# rock.net
KiCad netlist of a schematic drawn in Altium Designer
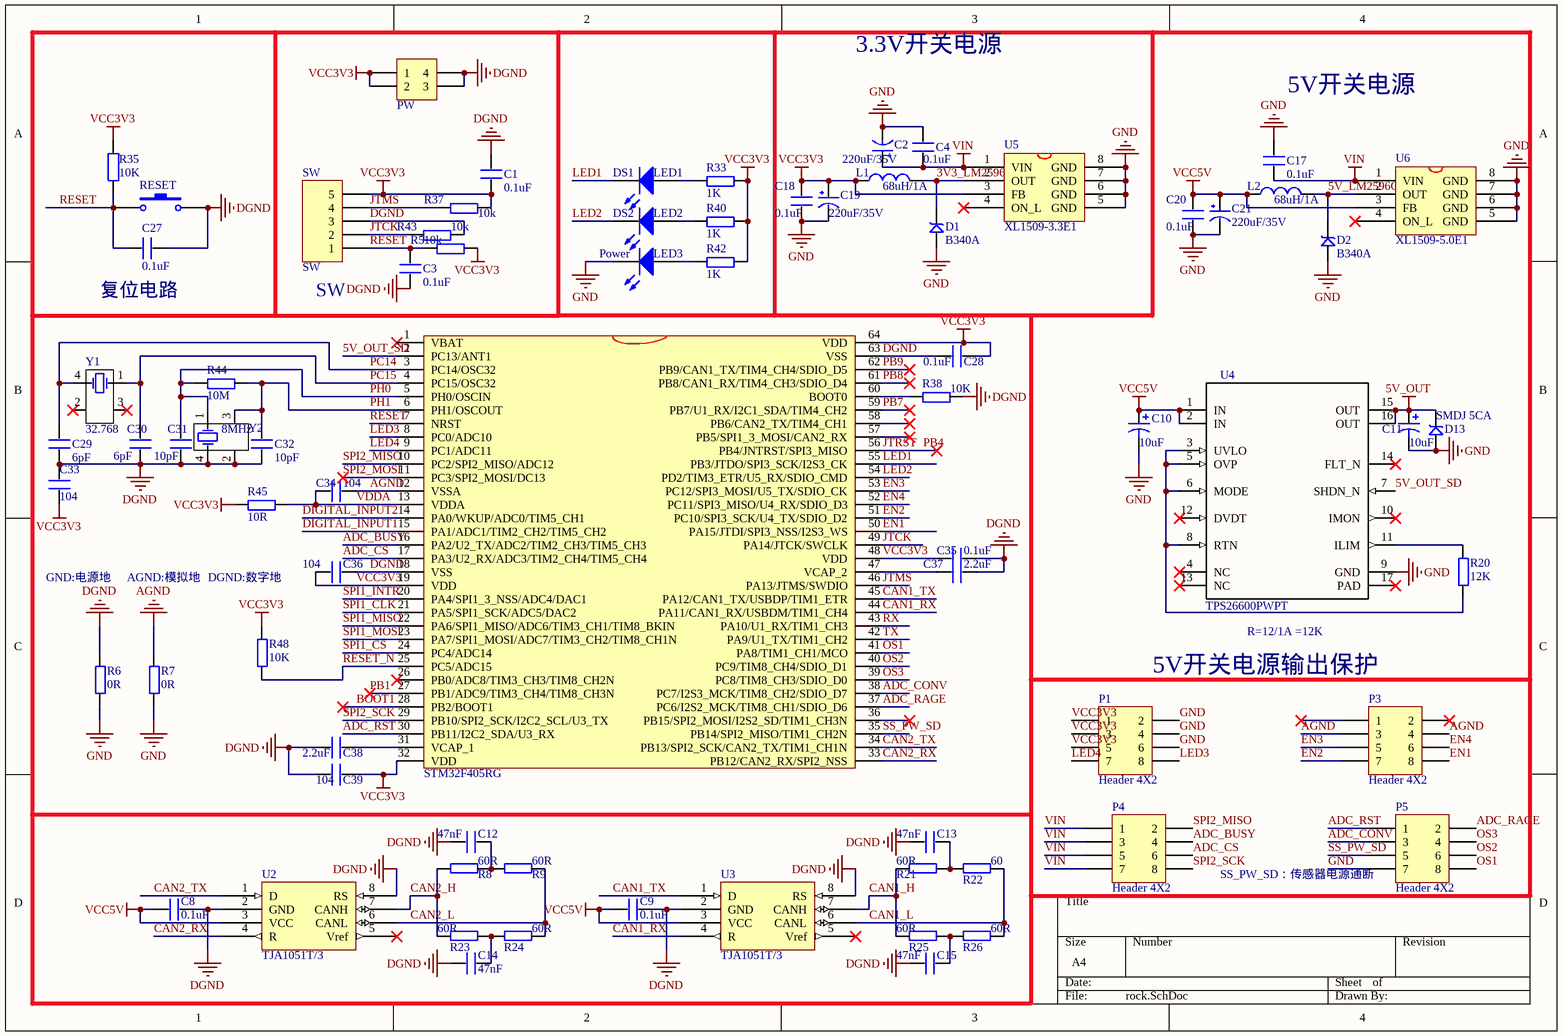
[diagram p0: rock.SchDoc]

(export (version "E")
  (design (tool "Eeschema 10.0.6"))
  (components
    (comp (ref "C1") (value "0.1uF") (footprint "0603") (libsource (lib "MiniSTM32 V3.0封装库") (part "C")))
    (comp (ref "C2")
      (value "220uF/35V")
      (footprint "C-RB-S8")
      (libsource (lib "MiniSTM32 V3.0封装库") (part "CAP"))
    )
    (comp (ref "C3") (value "0.1uF") (footprint "0603") (libsource (lib "MiniSTM32 V3.0封装库") (part "C")))
    (comp (ref "C4") (value "0.1uF") (footprint "0603") (libsource (lib "MiniSTM32 V3.0封装库") (part "C")))
    (comp (ref "C8") (value "0.1uF") (footprint "0603") (libsource (lib "MiniSTM32 V3.0封装库") (part "C")))
    (comp (ref "C9") (value "0.1uF") (footprint "0603") (libsource (lib "MiniSTM32 V3.0封装库") (part "C")))
    (comp (ref "C10")
      (value "10uF")
      (footprint "CAP-3216")
      (description "Polarized Capacitor (Surface Mount)")
      (fields (field (name "Comment") "Cap Pol3") (field (name "PUBLISHER") "Altium Limited"))
      (libsource (lib "Miscellaneous Devices") (part "Cap Pol3"))
    )
    (comp (ref "C11")
      (value "10uF")
      (footprint "CAP-3216")
      (description "Polarized Capacitor (Surface Mount)")
      (fields (field (name "Comment") "Cap Pol3") (field (name "PUBLISHER") "Altium Limited"))
      (libsource (lib "Miscellaneous Devices") (part "Cap Pol3"))
    )
    (comp (ref "C12") (value "47nF") (footprint "0603") (libsource (lib "MiniSTM32 V3.0封装库") (part "C")))
    (comp (ref "C13") (value "47nF") (footprint "0603") (libsource (lib "MiniSTM32 V3.0封装库") (part "C")))
    (comp (ref "C14") (value "47nF") (footprint "0603") (libsource (lib "MiniSTM32 V3.0封装库") (part "C")))
    (comp (ref "C15") (value "47nF") (footprint "0603") (libsource (lib "MiniSTM32 V3.0封装库") (part "C")))
    (comp (ref "C17") (value "0.1uF") (footprint "0603") (libsource (lib "MiniSTM32 V3.0封装库") (part "C")))
    (comp (ref "C18") (value "0.1uF") (footprint "0603") (libsource (lib "MiniSTM32 V3.0封装库") (part "C")))
    (comp (ref "C19") (value "220uF/35V") (footprint "C-RB-S8") (libsource (lib "") (part "CAP_1")))
    (comp (ref "C20") (value "0.1uF") (footprint "0603") (libsource (lib "MiniSTM32 V3.0封装库") (part "C")))
    (comp (ref "C21") (value "220uF/35V") (footprint "C-RB-S8") (libsource (lib "") (part "CAP_1")))
    (comp (ref "C27") (value "0.1uF") (footprint "0603") (libsource (lib "MiniSTM32 V3.0封装库") (part "C")))
    (comp (ref "C28") (value "0.1uF") (footprint "0603") (libsource (lib "MiniSTM32 V3.0封装库") (part "C")))
    (comp (ref "C29") (value "6pF") (footprint "0603") (libsource (lib "MiniSTM32 V3.0封装库") (part "C")))
    (comp (ref "C30") (value "6pF") (footprint "0603") (libsource (lib "MiniSTM32 V3.0封装库") (part "C")))
    (comp (ref "C31") (value "10pF") (footprint "0603") (libsource (lib "MiniSTM32 V3.0封装库") (part "C")))
    (comp (ref "C32") (value "10pF") (footprint "0603") (libsource (lib "MiniSTM32 V3.0封装库") (part "C")))
    (comp (ref "C33") (value "104") (footprint "0603") (libsource (lib "MiniSTM32 V3.0封装库") (part "C")))
    (comp (ref "C34") (value "104") (footprint "0603") (libsource (lib "MiniSTM32 V3.0封装库") (part "C")))
    (comp (ref "C35") (value "0.1uF") (footprint "0603") (libsource (lib "MiniSTM32 V3.0封装库") (part "C")))
    (comp (ref "C36") (value "104") (footprint "0603") (libsource (lib "MiniSTM32 V3.0封装库") (part "C")))
    (comp (ref "C37") (value "2.2uF") (footprint "0603") (libsource (lib "MiniSTM32 V3.0封装库") (part "C")))
    (comp (ref "C38") (value "2.2uF") (footprint "0603") (libsource (lib "MiniSTM32 V3.0封装库") (part "C")))
    (comp (ref "C39") (value "104") (footprint "0603") (libsource (lib "MiniSTM32 V3.0封装库") (part "C")))
    (comp (ref "D1")
      (value "B340A")
      (footprint "DO-214AC")
      (description "TVS")
      (libsource (lib "MiniSTM32 V3.0封装库") (part "SMBJ"))
    )
    (comp (ref "D2")
      (value "B340A")
      (footprint "DO-214AC")
      (description "TVS")
      (libsource (lib "MiniSTM32 V3.0封装库") (part "SMBJ"))
    )
    (comp (ref "D13")
      (value "SMDJ 5CA")
      (footprint "SMC")
      (description "SMDJ5.0CA")
      (fields
        (field (name "TERABITS PART NUMBER") "1D-0000001-XX")
        (field (name "MANUFACTURE PART NUMBER") "SMBJ 6.5CA")
      )
      (libsource (lib "new") (part "SMBJ 6.5CA"))
    )
    (comp (ref "DS1")
      (value "LED1")
      (footprint "0603")
      (description "Typical RED, GREEN, YELLOW, AMBER GaAs LED")
      (fields (field (name "PUBLISHER") "Altium Limited"))
      (libsource (lib "MiniSTM32 V3.0封装库") (part "LED2"))
    )
    (comp (ref "DS2")
      (value "LED2")
      (footprint "0603")
      (description "Typical RED, GREEN, YELLOW, AMBER GaAs LED")
      (fields (field (name "PUBLISHER") "Altium Limited"))
      (libsource (lib "MiniSTM32 V3.0封装库") (part "LED2"))
    )
    (comp (ref "L1")
      (value "68uH/1A")
      (footprint "6045")
      (description "电感")
      (fields (field (name "Comment") "SWPA6045S680MT") (field (name "PUBLISHER") "Altium Limited"))
      (libsource (lib "Song") (part "Inductor"))
    )
    (comp (ref "L2")
      (value "68uH/1A")
      (footprint "6045")
      (description "电感")
      (fields (field (name "Comment") "SWPA6045S680MT") (field (name "PUBLISHER") "Altium Limited"))
      (libsource (lib "Song") (part "Inductor"))
    )
    (comp (ref "P1")
      (value "Header 4X2")
      (footprint "HDR4X2_A_Tiepian")
      (description "接插件")
      (fields (field (name "PUBLISHER") "Altium Limited"))
      (libsource (lib "Song") (part "Header 4X2"))
    )
    (comp (ref "P3")
      (value "Header 4X2")
      (footprint "HDR4X2_A_Tiepian")
      (description "接插件")
      (fields (field (name "PUBLISHER") "Altium Limited"))
      (libsource (lib "Song") (part "Header 4X2"))
    )
    (comp (ref "P4")
      (value "Header 4X2")
      (footprint "HDR4X2_A_Tiepian")
      (description "接插件")
      (fields (field (name "PUBLISHER") "Altium Limited"))
      (libsource (lib "Song") (part "Header 4X2"))
    )
    (comp (ref "P5")
      (value "Header 4X2")
      (footprint "HDR4X2_A_Tiepian")
      (description "接插件")
      (fields (field (name "PUBLISHER") "Altium Limited"))
      (libsource (lib "Song") (part "Header 4X2"))
    )
    (comp (ref "Power")
      (value "LED3")
      (footprint "0603")
      (description "Typical RED, GREEN, YELLOW, AMBER GaAs LED")
      (fields (field (name "PUBLISHER") "Altium Limited"))
      (libsource (lib "MiniSTM32 V3.0封装库") (part "LED2"))
    )
    (comp (ref "PW")
      (value "Header 2X2A")
      (footprint "HDR2X2_A")
      (description "接插件")
      (fields (field (name "PUBLISHER") "Altium Limited"))
      (libsource (lib "Song") (part "Header 2X2A"))
    )
    (comp (ref "R5") (value "10k") (footprint "0603") (libsource (lib "MiniSTM32 V3.0封装库") (part "R")))
    (comp (ref "R6")
      (value "0R")
      (footprint "0603")
      (description "Res,1K,0603")
      (libsource (lib "new") (part "R_1K"))
    )
    (comp (ref "R7")
      (value "0R")
      (footprint "0603")
      (description "Res,1K,0603")
      (libsource (lib "new") (part "R_1K"))
    )
    (comp (ref "R8")
      (value "120R")
      (footprint "0603")
      (fields (field (name "ALTIUM_UNNAMED_1") "60R"))
      (libsource (lib "MiniSTM32 V3.0封装库") (part "R"))
    )
    (comp (ref "R9")
      (value "120R")
      (footprint "0603")
      (fields (field (name "ALTIUM_UNNAMED_1") "60R"))
      (libsource (lib "MiniSTM32 V3.0封装库") (part "R"))
    )
    (comp (ref "R20") (value "12K") (footprint "0603") (libsource (lib "WARSHIP") (part "R")))
    (comp (ref "R21")
      (value "120R")
      (footprint "0603")
      (fields (field (name "ALTIUM_UNNAMED_1") "60R"))
      (libsource (lib "MiniSTM32 V3.0封装库") (part "R"))
    )
    (comp (ref "R22")
      (value "120R")
      (footprint "0603")
      (fields (field (name "ALTIUM_UNNAMED_1") "60"))
      (libsource (lib "MiniSTM32 V3.0封装库") (part "R"))
    )
    (comp (ref "R23")
      (value "120R")
      (footprint "0603")
      (fields (field (name "ALTIUM_UNNAMED_1") "60R"))
      (libsource (lib "MiniSTM32 V3.0封装库") (part "R"))
    )
    (comp (ref "R24")
      (value "120R")
      (footprint "0603")
      (fields (field (name "ALTIUM_UNNAMED_1") "60R"))
      (libsource (lib "MiniSTM32 V3.0封装库") (part "R"))
    )
    (comp (ref "R25")
      (value "120R")
      (footprint "0603")
      (fields (field (name "ALTIUM_UNNAMED_1") "60R"))
      (libsource (lib "MiniSTM32 V3.0封装库") (part "R"))
    )
    (comp (ref "R26")
      (value "120R")
      (footprint "0603")
      (fields (field (name "ALTIUM_UNNAMED_1") "60R"))
      (libsource (lib "MiniSTM32 V3.0封装库") (part "R"))
    )
    (comp (ref "R33") (value "1K") (footprint "0603") (libsource (lib "MiniSTM32 V3.0封装库") (part "R")))
    (comp (ref "R35")
      (value "10K")
      (footprint "0603")
      (description "贴片电阻")
      (fields (field (name "PUBLISHER") "Altium Limited"))
      (libsource (lib "Song") (part "Res1"))
    )
    (comp (ref "R37") (value "10k") (footprint "0603") (libsource (lib "MiniSTM32 V3.0封装库") (part "R")))
    (comp (ref "R38") (value "10K") (footprint "0603") (libsource (lib "MiniSTM32 V3.0封装库") (part "R")))
    (comp (ref "R40") (value "1K") (footprint "0603") (libsource (lib "MiniSTM32 V3.0封装库") (part "R")))
    (comp (ref "R42") (value "1K") (footprint "0603") (libsource (lib "MiniSTM32 V3.0封装库") (part "R")))
    (comp (ref "R43") (value "10k") (footprint "0603") (libsource (lib "MiniSTM32 V3.0封装库") (part "R")))
    (comp (ref "R44") (value "10M") (footprint "0603") (libsource (lib "MiniSTM32 V3.0封装库") (part "R")))
    (comp (ref "R45") (value "10R") (footprint "0603") (libsource (lib "MiniSTM32 V3.0封装库") (part "R")))
    (comp (ref "R48") (value "10K") (footprint "0603") (libsource (lib "MiniSTM32 V3.0封装库") (part "R")))
    (comp (ref "RESET")
      (value "SW-PB")
      (footprint "SW_PB2_A2")
      (description "微动开关")
      (fields (field (name "PUBLISHER") "Altium Limited"))
      (libsource (lib "Song") (part "SW-PB"))
    )
    (comp (ref "STM32F405RG")
      (value "STM")
      (footprint "LQFP-64")
      (description "STM32F405RG_64Pins")
      (fields (field (name "PUBLISHER") "Altium Limited"))
      (libsource (lib "Song") (part "STM32F405RG"))
    )
    (comp (ref "SW")
      (value "SW")
      (footprint "HDR5X1_SW _Tiepian")
      (description "XH插座 1*5P 2.54mm")
      (fields (field (name "PUBLISHER") "Altium Limited"))
      (libsource (lib "Song") (part "Header 5"))
    )
    (comp (ref "U2")
      (value "TJA1051T/3")
      (footprint "SOP-8")
      (libsource (lib "WARSHIP") (part "SN65HVD230D"))
    )
    (comp (ref "U3")
      (value "TJA1051T/3")
      (footprint "SOP-8")
      (libsource (lib "WARSHIP") (part "SN65HVD230D"))
    )
    (comp (ref "U4")
      (value "TPS26600PWPT")
      (footprint "PWP0016H_N")
      (fields (field (name "PARTNUMBER") "TPS26600PWPR") (field (name "MANUFACTURER") "Texas Instruments"))
      (libsource (lib "TPS2660") (part "TPS26600PWPR"))
    )
    (comp (ref "U5")
      (value "XL1509-3.3E1")
      (footprint "SOIC8_N")
      (libsource (lib "Song") (part "XL1509-3.3V/5V/12V"))
    )
    (comp (ref "U6")
      (value "XL1509-5.0E1")
      (footprint "SOIC8_N")
      (libsource (lib "Song") (part "XL1509-3.3V/5V/12V"))
    )
    (comp (ref "Y1")
      (value "32.768")
      (footprint "XTAL_8x3.8")
      (description "Q13MC3062000600")
      (fields (field (name "Comment") "MC306"))
      (libsource (lib "Song") (part "XTAL_8x3.8"))
    )
    (comp (ref "Y2")
      (value "8MHz")
      (footprint "XTAL_5x3.2")
      (description "ABM3B-8.000MHZ/10pF")
      (fields (field (name "Comment") "ABM3B-8.000MHZ-10-1-U-T"))
      (libsource (lib "Song") (part "XTAL_8x3.8"))
    )
  )
  (nets
    (net (code "1") (name "/3V3_LM2596OUT") (class "Default")
      (node (ref "D1") (pin "2") (pintype "passive"))
      (node (ref "L1") (pin "2") (pinfunction "2_2") (pintype "passive"))
      (node (ref "U5") (pin "2") (pinfunction "OUT_2") (pintype "passive"))
    )
    (net (code "2") (name "/5V_LM2596OUT") (class "Default")
      (node (ref "D2") (pin "2") (pintype "passive"))
      (node (ref "L2") (pin "2") (pinfunction "2_2") (pintype "passive"))
      (node (ref "U6") (pin "2") (pinfunction "OUT_2") (pintype "passive"))
    )
    (net (code "3") (name "/5V_OUT_SD") (class "Default")
      (node (ref "STM32F405RG") (pin "2") (pinfunction "PC13/ANT1_2") (pintype "passive"))
      (node (ref "U4") (pin "7") (pinfunction "SHDN_N_7") (pintype "input"))
    )
    (net (code "4") (name "/ADC_BUSY") (class "Default")
      (node (ref "P4") (pin "4") (pinfunction "4_4") (pintype "passive"))
      (node (ref "STM32F405RG") (pin "16") (pinfunction "PA2/U2_TX/ADC2/TIM2_CH3/TIM5_CH3_16") (pintype "passive"))
    )
    (net (code "5") (name "/ADC_CONV") (class "Default")
      (node (ref "P5") (pin "3") (pinfunction "3_3") (pintype "passive"))
      (node (ref "STM32F405RG") (pin "38") (pinfunction "PC7/I2S3_MCK/TIM8_CH2/SDIO_D7_38") (pintype "passive"))
    )
    (net (code "6") (name "/ADC_CS") (class "Default")
      (node (ref "P4") (pin "6") (pinfunction "6_6") (pintype "passive"))
      (node (ref "STM32F405RG") (pin "17") (pinfunction "PA3/U2_RX/ADC3/TIM2_CH4/TIM5_CH4_17") (pintype "passive"))
    )
    (net (code "7") (name "/ADC_RAGE") (class "Default")
      (node (ref "P5") (pin "2") (pinfunction "2_2") (pintype "passive"))
      (node (ref "STM32F405RG") (pin "37") (pinfunction "PC6/I2S2_MCK/TIM8_CH1/SDIO_D6_37") (pintype "passive"))
    )
    (net (code "8") (name "/ADC_RST") (class "Default")
      (node (ref "P5") (pin "1") (pinfunction "1_1") (pintype "passive"))
      (node (ref "STM32F405RG") (pin "30") (pinfunction "PB11/I2C2_SDA/U3_RX_30") (pintype "passive"))
    )
    (net (code "9") (name "/BOOT1") (class "Default")
      (node (ref "STM32F405RG") (pin "28") (pinfunction "PB2/BOOT1_28") (pintype "passive+no_connect"))
    )
    (net (code "10") (name "/CAN1_H") (class "Default")
      (node (ref "R21") (pin "2") (pintype "passive"))
      (node (ref "R25") (pin "2") (pintype "passive"))
      (node (ref "U3") (pin "7") (pinfunction "CANH_7") (pintype "bidirectional"))
    )
    (net (code "11") (name "/CAN1_L") (class "Default")
      (node (ref "R22") (pin "1") (pintype "passive"))
      (node (ref "R26") (pin "1") (pintype "passive"))
      (node (ref "U3") (pin "6") (pinfunction "CANL_6") (pintype "bidirectional"))
    )
    (net (code "12") (name "/CAN1_RX") (class "Default")
      (node (ref "STM32F405RG") (pin "44") (pinfunction "PA11/CAN1_RX/USBDM/TIM1_CH4_44") (pintype "passive"))
      (node (ref "U3") (pin "4") (pinfunction "R_4") (pintype "output"))
    )
    (net (code "13") (name "/CAN1_TX") (class "Default")
      (node (ref "STM32F405RG") (pin "45") (pinfunction "PA12/CAN1_TX/USBDP/TIM1_ETR_45") (pintype "passive"))
      (node (ref "U3") (pin "1") (pinfunction "D_1") (pintype "input"))
    )
    (net (code "14") (name "/CAN2_H") (class "Default")
      (node (ref "R23") (pin "2") (pintype "passive"))
      (node (ref "R8") (pin "2") (pintype "passive"))
      (node (ref "U2") (pin "7") (pinfunction "CANH_7") (pintype "bidirectional"))
    )
    (net (code "15") (name "/CAN2_L") (class "Default")
      (node (ref "R24") (pin "1") (pintype "passive"))
      (node (ref "R9") (pin "1") (pintype "passive"))
      (node (ref "U2") (pin "6") (pinfunction "CANL_6") (pintype "bidirectional"))
    )
    (net (code "16") (name "/CAN2_RX") (class "Default")
      (node (ref "STM32F405RG") (pin "33") (pinfunction "PB12/CAN2_RX/SPI2_NSS_33") (pintype "passive"))
      (node (ref "U2") (pin "4") (pinfunction "R_4") (pintype "output"))
    )
    (net (code "17") (name "/CAN2_TX") (class "Default")
      (node (ref "STM32F405RG") (pin "34") (pinfunction "PB13/SPI2_SCK/CAN2_TX/TIM1_CH1N_34") (pintype "passive"))
      (node (ref "U2") (pin "1") (pinfunction "D_1") (pintype "input"))
    )
    (net (code "18") (name "/DIGITAL_INPUT1") (class "Default")
      (node (ref "STM32F405RG") (pin "15") (pinfunction "PA1/ADC1/TIM2_CH2/TIM5_CH2_15") (pintype "passive"))
    )
    (net (code "19") (name "/DIGITAL_INPUT2") (class "Default")
      (node (ref "STM32F405RG") (pin "14") (pinfunction "PA0/WKUP/ADC0/TIM5_CH1_14") (pintype "passive"))
    )
    (net (code "20") (name "/EN1") (class "Default")
      (node (ref "P3") (pin "8") (pinfunction "8_8") (pintype "passive"))
      (node (ref "STM32F405RG") (pin "50") (pinfunction "PA15/JTDI/SPI3_NSS/I2S3_WS_50") (pintype "passive"))
    )
    (net (code "21") (name "/EN2") (class "Default")
      (node (ref "P3") (pin "7") (pinfunction "7_7") (pintype "passive"))
      (node (ref "STM32F405RG") (pin "51") (pinfunction "PC10/SPI3_SCK/U4_TX/SDIO_D2_51") (pintype "passive"))
    )
    (net (code "22") (name "/EN3") (class "Default")
      (node (ref "P3") (pin "5") (pinfunction "5_5") (pintype "passive"))
      (node (ref "STM32F405RG") (pin "53") (pinfunction "PC12/SPI3_MOSI/U5_TX/SDIO_CK_53") (pintype "passive"))
    )
    (net (code "23") (name "/EN4") (class "Default")
      (node (ref "P3") (pin "6") (pinfunction "6_6") (pintype "passive"))
      (node (ref "STM32F405RG") (pin "52") (pinfunction "PC11/SPI3_MISO/U4_RX/SDIO_D3_52") (pintype "passive"))
    )
    (net (code "24") (name "/JTCK") (class "Default")
      (node (ref "R43") (pin "1") (pintype "passive"))
      (node (ref "STM32F405RG") (pin "49") (pinfunction "PA14/JTCK/SWCLK_49") (pintype "passive"))
      (node (ref "SW") (pin "2") (pinfunction "2_2") (pintype "passive"))
    )
    (net (code "25") (name "/JTMS") (class "Default")
      (node (ref "R37") (pin "1") (pintype "passive"))
      (node (ref "STM32F405RG") (pin "46") (pinfunction "PA13/JTMS/SWDIO_46") (pintype "passive"))
      (node (ref "SW") (pin "4") (pinfunction "4_4") (pintype "passive"))
    )
    (net (code "26") (name "/JTRST") (class "Default")
      (node (ref "STM32F405RG") (pin "56") (pinfunction "PB4/JNTRST/SPI3_MISO_56") (pintype "passive+no_connect"))
    )
    (net (code "27") (name "/LED1") (class "Default")
      (node (ref "DS1") (pin "2") (pinfunction "K_2") (pintype "passive"))
      (node (ref "STM32F405RG") (pin "55") (pinfunction "PB3/JTDO/SPI3_SCK/I2S3_CK_55") (pintype "passive"))
    )
    (net (code "28") (name "/LED2") (class "Default")
      (node (ref "DS2") (pin "2") (pinfunction "K_2") (pintype "passive"))
      (node (ref "STM32F405RG") (pin "54") (pinfunction "PD2/TIM3_ETR/U5_RX/SDIO_CMD_54") (pintype "passive"))
    )
    (net (code "29") (name "/LED3") (class "Default")
      (node (ref "P1") (pin "8") (pinfunction "8_8") (pintype "passive"))
      (node (ref "STM32F405RG") (pin "8") (pinfunction "PC0/ADC10_8") (pintype "passive"))
    )
    (net (code "30") (name "/LED4") (class "Default")
      (node (ref "P1") (pin "7") (pinfunction "7_7") (pintype "passive"))
      (node (ref "STM32F405RG") (pin "9") (pinfunction "PC1/ADC11_9") (pintype "passive"))
    )
    (net (code "31") (name "/OS1") (class "Default")
      (node (ref "P5") (pin "8") (pinfunction "8_8") (pintype "passive"))
      (node (ref "STM32F405RG") (pin "41") (pinfunction "PA8/TIM1_CH1/MCO_41") (pintype "passive"))
    )
    (net (code "32") (name "/OS2") (class "Default")
      (node (ref "P5") (pin "6") (pinfunction "6_6") (pintype "passive"))
      (node (ref "STM32F405RG") (pin "40") (pinfunction "PC9/TIM8_CH4/SDIO_D1_40") (pintype "passive"))
    )
    (net (code "33") (name "/OS3") (class "Default")
      (node (ref "P5") (pin "4") (pinfunction "4_4") (pintype "passive"))
      (node (ref "STM32F405RG") (pin "39") (pinfunction "PC8/TIM8_CH3/SDIO_D0_39") (pintype "passive"))
    )
    (net (code "34") (name "/PB1") (class "Default")
      (node (ref "STM32F405RG") (pin "27") (pinfunction "PB1/ADC9/TIM3_CH4/TIM8_CH3N_27") (pintype "passive+no_connect"))
    )
    (net (code "35") (name "/PB7") (class "Default")
      (node (ref "STM32F405RG") (pin "59") (pinfunction "PB7/U1_RX/I2C1_SDA/TIM4_CH2_59") (pintype "passive+no_connect"))
    )
    (net (code "36") (name "/PB8") (class "Default")
      (node (ref "STM32F405RG") (pin "61") (pinfunction "PB8/CAN1_RX/TIM4_CH3/SDIO_D4_61") (pintype "passive+no_connect"))
    )
    (net (code "37") (name "/PB9") (class "Default")
      (node (ref "STM32F405RG") (pin "62") (pinfunction "PB9/CAN1_TX/TIM4_CH4/SDIO_D5_62") (pintype "passive+no_connect"))
    )
    (net (code "38") (name "/PC14") (class "Default")
      (node (ref "C29") (pin "2") (pintype "passive"))
      (node (ref "STM32F405RG") (pin "3") (pinfunction "PC14/OSC32_3") (pintype "passive"))
      (node (ref "Y1") (pin "4") (pinfunction "OSC1_4") (pintype "passive"))
    )
    (net (code "39") (name "/PC15") (class "Default")
      (node (ref "C30") (pin "2") (pintype "passive"))
      (node (ref "STM32F405RG") (pin "4") (pinfunction "PC15/OSC32_4") (pintype "passive"))
      (node (ref "Y1") (pin "1") (pinfunction "OSC2_1") (pintype "passive"))
    )
    (net (code "40") (name "/PH0") (class "Default")
      (node (ref "C31") (pin "2") (pintype "passive"))
      (node (ref "R44") (pin "1") (pintype "passive"))
      (node (ref "STM32F405RG") (pin "5") (pinfunction "PH0/OSCIN_5") (pintype "passive"))
      (node (ref "Y2") (pin "1") (pinfunction "OSC2_1") (pintype "passive"))
    )
    (net (code "41") (name "/PH1") (class "Default")
      (node (ref "C32") (pin "2") (pintype "passive"))
      (node (ref "R44") (pin "2") (pintype "passive"))
      (node (ref "STM32F405RG") (pin "6") (pinfunction "PH1/OSCOUT_6") (pintype "passive"))
      (node (ref "Y2") (pin "3") (pinfunction "NC_3") (pintype "passive"))
    )
    (net (code "42") (name "/RESET") (class "Default")
      (node (ref "C27") (pin "1") (pintype "passive"))
      (node (ref "C3") (pin "2") (pintype "passive"))
      (node (ref "R35") (pin "1") (pinfunction "1_1") (pintype "passive"))
      (node (ref "R5") (pin "1") (pintype "passive"))
      (node (ref "RESET") (pin "1") (pinfunction "1_1") (pintype "passive"))
      (node (ref "STM32F405RG") (pin "7") (pinfunction "NRST_7") (pintype "passive"))
      (node (ref "SW") (pin "1") (pinfunction "1_1") (pintype "passive"))
    )
    (net (code "43") (name "/RESET_N") (class "Default")
      (node (ref "R48") (pin "1") (pintype "passive"))
      (node (ref "STM32F405RG") (pin "25") (pinfunction "PC5/ADC15_25") (pintype "passive"))
    )
    (net (code "44") (name "/RX") (class "Default")
      (node (ref "STM32F405RG") (pin "43") (pinfunction "PA10/U1_RX/TIM1_CH3_43") (pintype "passive"))
    )
    (net (code "45") (name "/SPI1_CLK") (class "Default")
      (node (ref "STM32F405RG") (pin "21") (pinfunction "PA5/SPI1_SCK/ADC5/DAC2_21") (pintype "passive"))
    )
    (net (code "46") (name "/SPI1_CS") (class "Default")
      (node (ref "STM32F405RG") (pin "24") (pinfunction "PC4/ADC14_24") (pintype "passive"))
    )
    (net (code "47") (name "/SPI1_INTR") (class "Default")
      (node (ref "STM32F405RG") (pin "20") (pinfunction "PA4/SPI1_3_NSS/ADC4/DAC1_20") (pintype "passive"))
    )
    (net (code "48") (name "/SPI1_MISO") (class "Default")
      (node (ref "STM32F405RG") (pin "22") (pinfunction "PA6/SPI1_MISO/ADC6/TIM3_CH1/TIM8_BKIN_22") (pintype "passive"))
    )
    (net (code "49") (name "/SPI1_MOSI") (class "Default")
      (node (ref "STM32F405RG") (pin "23") (pinfunction "PA7/SPI1_MOSI/ADC7/TIM3_CH2/TIM8_CH1N_23") (pintype "passive"))
    )
    (net (code "50") (name "/SPI2_MISO") (class "Default")
      (node (ref "P4") (pin "2") (pinfunction "2_2") (pintype "passive"))
      (node (ref "STM32F405RG") (pin "10") (pinfunction "PC2/SPI2_MISO/ADC12_10") (pintype "passive"))
    )
    (net (code "51") (name "/SPI2_MOSI") (class "Default")
      (node (ref "STM32F405RG") (pin "11") (pinfunction "PC3/SPI2_MOSI/DC13_11") (pintype "passive+no_connect"))
    )
    (net (code "52") (name "/SPI2_SCK") (class "Default")
      (node (ref "P4") (pin "8") (pinfunction "8_8") (pintype "passive"))
      (node (ref "STM32F405RG") (pin "29") (pinfunction "PB10/SPI2_SCK/I2C2_SCL/U3_TX_29") (pintype "passive"))
    )
    (net (code "53") (name "/SS_PW_SD") (class "Default")
      (node (ref "P5") (pin "5") (pinfunction "5_5") (pintype "passive"))
      (node (ref "STM32F405RG") (pin "35") (pinfunction "PB14/SPI2_MISO/TIM1_CH2N_35") (pintype "passive"))
    )
    (net (code "54") (name "/TX") (class "Default")
      (node (ref "STM32F405RG") (pin "42") (pinfunction "PA9/U1_TX/TIM1_CH2_42") (pintype "passive"))
    )
    (net (code "55") (name "/VDDA") (class "Default")
      (node (ref "C34") (pin "2") (pintype "passive"))
      (node (ref "R45") (pin "2") (pintype "passive"))
      (node (ref "STM32F405RG") (pin "13") (pinfunction "VDDA_13") (pintype "passive"))
    )
    (net (code "56") (name "5V_OUT") (class "Default")
      (node (ref "C11") (pin "1") (pinfunction "1_1") (pintype "passive"))
      (node (ref "D13") (pin "2") (pintype "passive"))
      (node (ref "U4") (pin "15") (pinfunction "OUT_15") (pintype "power_in"))
      (node (ref "U4") (pin "16") (pinfunction "OUT_16") (pintype "power_in"))
    )
    (net (code "57") (name "AGND") (class "Default")
      (node (ref "C34") (pin "1") (pintype "passive"))
      (node (ref "P3") (pin "3") (pinfunction "3_3") (pintype "passive"))
      (node (ref "P3") (pin "4") (pinfunction "4_4") (pintype "passive"))
      (node (ref "R7") (pin "2") (pintype "passive"))
      (node (ref "STM32F405RG") (pin "12") (pinfunction "VSSA_12") (pintype "passive"))
    )
    (net (code "58") (name "DGND") (class "Default")
      (node (ref "C1") (pin "1") (pintype "passive"))
      (node (ref "C12") (pin "2") (pintype "passive"))
      (node (ref "C13") (pin "2") (pintype "passive"))
      (node (ref "C14") (pin "2") (pintype "passive"))
      (node (ref "C15") (pin "2") (pintype "passive"))
      (node (ref "C27") (pin "2") (pintype "passive"))
      (node (ref "C28") (pin "1") (pintype "passive"))
      (node (ref "C29") (pin "1") (pintype "passive"))
      (node (ref "C3") (pin "1") (pintype "passive"))
      (node (ref "C30") (pin "1") (pintype "passive"))
      (node (ref "C31") (pin "1") (pintype "passive"))
      (node (ref "C32") (pin "1") (pintype "passive"))
      (node (ref "C33") (pin "2") (pintype "passive"))
      (node (ref "C35") (pin "2") (pintype "passive"))
      (node (ref "C36") (pin "2") (pintype "passive"))
      (node (ref "C37") (pin "2") (pintype "passive"))
      (node (ref "C38") (pin "1") (pintype "passive"))
      (node (ref "C39") (pin "1") (pintype "passive"))
      (node (ref "C8") (pin "1") (pintype "passive"))
      (node (ref "C9") (pin "1") (pintype "passive"))
      (node (ref "PW") (pin "3") (pinfunction "3_3") (pintype "passive"))
      (node (ref "PW") (pin "4") (pinfunction "4_4") (pintype "passive"))
      (node (ref "R38") (pin "2") (pintype "passive"))
      (node (ref "R43") (pin "2") (pintype "passive"))
      (node (ref "R6") (pin "2") (pintype "passive"))
      (node (ref "RESET") (pin "2") (pinfunction "2_2") (pintype "passive"))
      (node (ref "STM32F405RG") (pin "18") (pinfunction "VSS_18") (pintype "passive"))
      (node (ref "STM32F405RG") (pin "63") (pinfunction "VSS_63") (pintype "passive"))
      (node (ref "SW") (pin "3") (pinfunction "3_3") (pintype "passive"))
      (node (ref "U2") (pin "2") (pinfunction "GND_2") (pintype "power_in"))
      (node (ref "U2") (pin "8") (pinfunction "RS_8") (pintype "input"))
      (node (ref "U3") (pin "2") (pinfunction "GND_2") (pintype "power_in"))
      (node (ref "U3") (pin "8") (pinfunction "RS_8") (pintype "input"))
      (node (ref "Y2") (pin "2") (pinfunction "NC_2") (pintype "passive"))
      (node (ref "Y2") (pin "4") (pinfunction "OSC1_4") (pintype "passive"))
    )
    (net (code "59") (name "GND") (class "Default")
      (node (ref "C10") (pin "2") (pinfunction "2_2") (pintype "passive"))
      (node (ref "C11") (pin "2") (pinfunction "2_2") (pintype "passive"))
      (node (ref "C17") (pin "1") (pintype "passive"))
      (node (ref "C18") (pin "1") (pintype "passive"))
      (node (ref "C19") (pin "2") (pinfunction "GND_2") (pintype "passive"))
      (node (ref "C2") (pin "2") (pinfunction "GND_2") (pintype "passive"))
      (node (ref "C20") (pin "1") (pintype "passive"))
      (node (ref "C21") (pin "2") (pinfunction "GND_2") (pintype "passive"))
      (node (ref "C4") (pin "1") (pintype "passive"))
      (node (ref "D1") (pin "1") (pintype "passive"))
      (node (ref "D13") (pin "1") (pintype "passive"))
      (node (ref "D2") (pin "1") (pintype "passive"))
      (node (ref "P1") (pin "2") (pinfunction "2_2") (pintype "passive"))
      (node (ref "P1") (pin "4") (pinfunction "4_4") (pintype "passive"))
      (node (ref "P1") (pin "6") (pinfunction "6_6") (pintype "passive"))
      (node (ref "P5") (pin "7") (pinfunction "7_7") (pintype "passive"))
      (node (ref "Power") (pin "2") (pinfunction "K_2") (pintype "passive"))
      (node (ref "R6") (pin "1") (pintype "passive"))
      (node (ref "R7") (pin "1") (pintype "passive"))
      (node (ref "U4") (pin "9") (pinfunction "GND_9") (pintype "power_in"))
      (node (ref "U5") (pin "5") (pinfunction "GND_5") (pintype "passive"))
      (node (ref "U5") (pin "6") (pinfunction "GND_6") (pintype "passive"))
      (node (ref "U5") (pin "7") (pinfunction "GND_7") (pintype "passive"))
      (node (ref "U5") (pin "8") (pinfunction "GND_8") (pintype "passive"))
      (node (ref "U6") (pin "5") (pinfunction "GND_5") (pintype "passive"))
      (node (ref "U6") (pin "6") (pinfunction "GND_6") (pintype "passive"))
      (node (ref "U6") (pin "7") (pinfunction "GND_7") (pintype "passive"))
      (node (ref "U6") (pin "8") (pinfunction "GND_8") (pintype "passive"))
    )
    (net (code "60") (name "Net-(C12-Pad1)") (class "Default")
      (node (ref "C12") (pin "1") (pintype "passive"))
      (node (ref "R8") (pin "1") (pintype "passive"))
      (node (ref "R9") (pin "2") (pintype "passive"))
    )
    (net (code "61") (name "Net-(C13-Pad1)") (class "Default")
      (node (ref "C13") (pin "1") (pintype "passive"))
      (node (ref "R21") (pin "1") (pintype "passive"))
      (node (ref "R22") (pin "2") (pintype "passive"))
    )
    (net (code "62") (name "Net-(C14-Pad1)") (class "Default")
      (node (ref "C14") (pin "1") (pintype "passive"))
      (node (ref "R23") (pin "1") (pintype "passive"))
      (node (ref "R24") (pin "2") (pintype "passive"))
    )
    (net (code "63") (name "Net-(C15-Pad1)") (class "Default")
      (node (ref "C15") (pin "1") (pintype "passive"))
      (node (ref "R25") (pin "1") (pintype "passive"))
      (node (ref "R26") (pin "2") (pintype "passive"))
    )
    (net (code "64") (name "Net-(DS1-A)") (class "Default")
      (node (ref "DS1") (pin "1") (pinfunction "A_1") (pintype "passive"))
      (node (ref "R33") (pin "1") (pintype "passive"))
    )
    (net (code "65") (name "Net-(DS2-A)") (class "Default")
      (node (ref "DS2") (pin "1") (pinfunction "A_1") (pintype "passive"))
      (node (ref "R40") (pin "1") (pintype "passive"))
    )
    (net (code "66") (name "Net-(Power-A)") (class "Default")
      (node (ref "Power") (pin "1") (pinfunction "A_1") (pintype "passive"))
      (node (ref "R42") (pin "1") (pintype "passive"))
    )
    (net (code "67") (name "Net-(STM32F405RG-BOOT0)") (class "Default")
      (node (ref "R38") (pin "1") (pintype "passive"))
      (node (ref "STM32F405RG") (pin "60") (pinfunction "BOOT0_60") (pintype "passive"))
    )
    (net (code "68") (name "Net-(STM32F405RG-VCAP_1)") (class "Default")
      (node (ref "C38") (pin "2") (pintype "passive"))
      (node (ref "STM32F405RG") (pin "31") (pinfunction "VCAP_1_31") (pintype "passive"))
    )
    (net (code "69") (name "Net-(STM32F405RG-VCAP_2)") (class "Default")
      (node (ref "C37") (pin "1") (pintype "passive"))
      (node (ref "STM32F405RG") (pin "47") (pinfunction "VCAP_2_47") (pintype "passive"))
    )
    (net (code "70") (name "Net-(U4-ILIM)") (class "Default")
      (node (ref "R20") (pin "2") (pintype "passive"))
      (node (ref "U4") (pin "11") (pinfunction "ILIM_11") (pintype "output"))
    )
    (net (code "71") (name "Net-(U4-MODE)") (class "Default")
      (node (ref "R20") (pin "1") (pintype "passive"))
      (node (ref "U4") (pin "3") (pinfunction "UVLO_3") (pintype "input"))
      (node (ref "U4") (pin "5") (pinfunction "OVP_5") (pintype "input"))
      (node (ref "U4") (pin "6") (pinfunction "MODE_6") (pintype "input"))
      (node (ref "U4") (pin "8") (pinfunction "RTN_8") (pintype "input"))
    )
    (net (code "72") (name "VCC3V3") (class "Default")
      (node (ref "C1") (pin "2") (pintype "passive"))
      (node (ref "C18") (pin "2") (pintype "passive"))
      (node (ref "C19") (pin "1") (pinfunction "VCC_1") (pintype "passive"))
      (node (ref "C28") (pin "2") (pintype "passive"))
      (node (ref "C33") (pin "1") (pintype "passive"))
      (node (ref "C35") (pin "1") (pintype "passive"))
      (node (ref "C36") (pin "1") (pintype "passive"))
      (node (ref "C39") (pin "2") (pintype "passive"))
      (node (ref "L1") (pin "1") (pinfunction "1_1") (pintype "passive"))
      (node (ref "P1") (pin "1") (pinfunction "1_1") (pintype "passive"))
      (node (ref "P1") (pin "3") (pinfunction "3_3") (pintype "passive"))
      (node (ref "P1") (pin "5") (pinfunction "5_5") (pintype "passive"))
      (node (ref "PW") (pin "1") (pinfunction "1_1") (pintype "passive"))
      (node (ref "PW") (pin "2") (pinfunction "2_2") (pintype "passive"))
      (node (ref "R33") (pin "2") (pintype "passive"))
      (node (ref "R35") (pin "2") (pinfunction "2_2") (pintype "passive"))
      (node (ref "R37") (pin "2") (pintype "passive"))
      (node (ref "R40") (pin "2") (pintype "passive"))
      (node (ref "R42") (pin "2") (pintype "passive"))
      (node (ref "R45") (pin "1") (pintype "passive"))
      (node (ref "R48") (pin "2") (pintype "passive"))
      (node (ref "R5") (pin "2") (pintype "passive"))
      (node (ref "STM32F405RG") (pin "19") (pinfunction "VDD_19") (pintype "passive"))
      (node (ref "STM32F405RG") (pin "32") (pinfunction "VDD_32") (pintype "passive"))
      (node (ref "STM32F405RG") (pin "48") (pinfunction "VDD_48") (pintype "passive"))
      (node (ref "STM32F405RG") (pin "64") (pinfunction "VDD_64") (pintype "passive"))
      (node (ref "SW") (pin "5") (pinfunction "5_5") (pintype "passive"))
      (node (ref "U5") (pin "3") (pinfunction "FB_3") (pintype "passive"))
    )
    (net (code "73") (name "VCC5V") (class "Default")
      (node (ref "C10") (pin "1") (pinfunction "1_1") (pintype "passive"))
      (node (ref "C20") (pin "2") (pintype "passive"))
      (node (ref "C21") (pin "1") (pinfunction "VCC_1") (pintype "passive"))
      (node (ref "C8") (pin "2") (pintype "passive"))
      (node (ref "C9") (pin "2") (pintype "passive"))
      (node (ref "L2") (pin "1") (pinfunction "1_1") (pintype "passive"))
      (node (ref "U2") (pin "3") (pinfunction "VCC_3") (pintype "power_in"))
      (node (ref "U3") (pin "3") (pinfunction "VCC_3") (pintype "power_in"))
      (node (ref "U4") (pin "1") (pinfunction "IN_1") (pintype "power_in"))
      (node (ref "U4") (pin "2") (pinfunction "IN_2") (pintype "power_in"))
      (node (ref "U6") (pin "3") (pinfunction "FB_3") (pintype "passive"))
    )
    (net (code "74") (name "VIN") (class "Default")
      (node (ref "C17") (pin "2") (pintype "passive"))
      (node (ref "C2") (pin "1") (pinfunction "VCC_1") (pintype "passive"))
      (node (ref "C4") (pin "2") (pintype "passive"))
      (node (ref "P4") (pin "1") (pinfunction "1_1") (pintype "passive"))
      (node (ref "P4") (pin "3") (pinfunction "3_3") (pintype "passive"))
      (node (ref "P4") (pin "5") (pinfunction "5_5") (pintype "passive"))
      (node (ref "P4") (pin "7") (pinfunction "7_7") (pintype "passive"))
      (node (ref "U5") (pin "1") (pinfunction "VIN_1") (pintype "passive"))
      (node (ref "U6") (pin "1") (pinfunction "VIN_1") (pintype "passive"))
    )
    (net (code "75") (name "unconnected-(P3-Pad1)") (class "Default")
      (node (ref "P3") (pin "1") (pinfunction "1_1") (pintype "passive+no_connect"))
    )
    (net (code "76") (name "unconnected-(P3-Pad2)") (class "Default")
      (node (ref "P3") (pin "2") (pinfunction "2_2") (pintype "passive+no_connect"))
    )
    (net (code "77") (name "unconnected-(STM32F405RG-PB0{slash}ADC8{slash}TIM3_CH3{slash}TIM8_CH2N-Pad26)") (class "Default")
      (node (ref "STM32F405RG") (pin "26") (pinfunction "PB0/ADC8/TIM3_CH3/TIM8_CH2N_26") (pintype "passive+no_connect"))
    )
    (net (code "78") (name "unconnected-(STM32F405RG-PB5{slash}SPI1_3_MOSI{slash}CAN2_RX-Pad57)") (class "Default")
      (node (ref "STM32F405RG") (pin "57") (pinfunction "PB5/SPI1_3_MOSI/CAN2_RX_57") (pintype "passive+no_connect"))
    )
    (net (code "79") (name "unconnected-(STM32F405RG-PB6{slash}CAN2_TX{slash}TIM4_CH1-Pad58)") (class "Default")
      (node (ref "STM32F405RG") (pin "58") (pinfunction "PB6/CAN2_TX/TIM4_CH1_58") (pintype "passive+no_connect"))
    )
    (net (code "80") (name "unconnected-(STM32F405RG-PB15{slash}SPI2_MOSI{slash}I2S2_SD{slash}TIM1_CH3N-Pad36)") (class "Default")
      (node (ref "STM32F405RG") (pin "36") (pinfunction "PB15/SPI2_MOSI/I2S2_SD/TIM1_CH3N_36") (pintype "passive+no_connect"))
    )
    (net (code "81") (name "unconnected-(STM32F405RG-VBAT-Pad1)") (class "Default")
      (node (ref "STM32F405RG") (pin "1") (pinfunction "VBAT_1") (pintype "passive+no_connect"))
    )
    (net (code "82") (name "unconnected-(U2-Vref-Pad5)") (class "Default")
      (node (ref "U2") (pin "5") (pinfunction "Vref_5") (pintype "output+no_connect"))
    )
    (net (code "83") (name "unconnected-(U3-Vref-Pad5)") (class "Default")
      (node (ref "U3") (pin "5") (pinfunction "Vref_5") (pintype "output+no_connect"))
    )
    (net (code "84") (name "unconnected-(U4-DVDT-Pad12)") (class "Default")
      (node (ref "U4") (pin "12") (pinfunction "DVDT_12") (pintype "input+no_connect"))
    )
    (net (code "85") (name "unconnected-(U4-FLT_N-Pad14)") (class "Default")
      (node (ref "U4") (pin "14") (pinfunction "FLT_N_14") (pintype "open_collector+no_connect"))
    )
    (net (code "86") (name "unconnected-(U4-IMON-Pad10)") (class "Default")
      (node (ref "U4") (pin "10") (pinfunction "IMON_10") (pintype "output+no_connect"))
    )
    (net (code "87") (name "unconnected-(U4-NC-Pad4)") (class "Default")
      (node (ref "U4") (pin "4") (pinfunction "NC_4") (pintype "passive+no_connect"))
    )
    (net (code "88") (name "unconnected-(U4-NC-Pad13)") (class "Default")
      (node (ref "U4") (pin "13") (pinfunction "NC_13") (pintype "passive+no_connect"))
    )
    (net (code "89") (name "unconnected-(U4-PAD-Pad17)") (class "Default")
      (node (ref "U4") (pin "17") (pinfunction "PAD_17") (pintype "power_in+no_connect"))
    )
    (net (code "90") (name "unconnected-(U5-ON_L-Pad4)") (class "Default")
      (node (ref "U5") (pin "4") (pinfunction "ON_L_4") (pintype "passive+no_connect"))
    )
    (net (code "91") (name "unconnected-(U6-ON_L-Pad4)") (class "Default")
      (node (ref "U6") (pin "4") (pinfunction "ON_L_4") (pintype "passive+no_connect"))
    )
    (net (code "92") (name "unconnected-(Y1-NC-Pad2)") (class "Default")
      (node (ref "Y1") (pin "2") (pinfunction "NC_2") (pintype "passive+no_connect"))
    )
    (net (code "93") (name "unconnected-(Y1-NC-Pad3)") (class "Default")
      (node (ref "Y1") (pin "3") (pinfunction "NC_3") (pintype "passive+no_connect"))
    )
  )
)
